# Teensy.net
KiCad netlist of a schematic drawn in Altium Designer
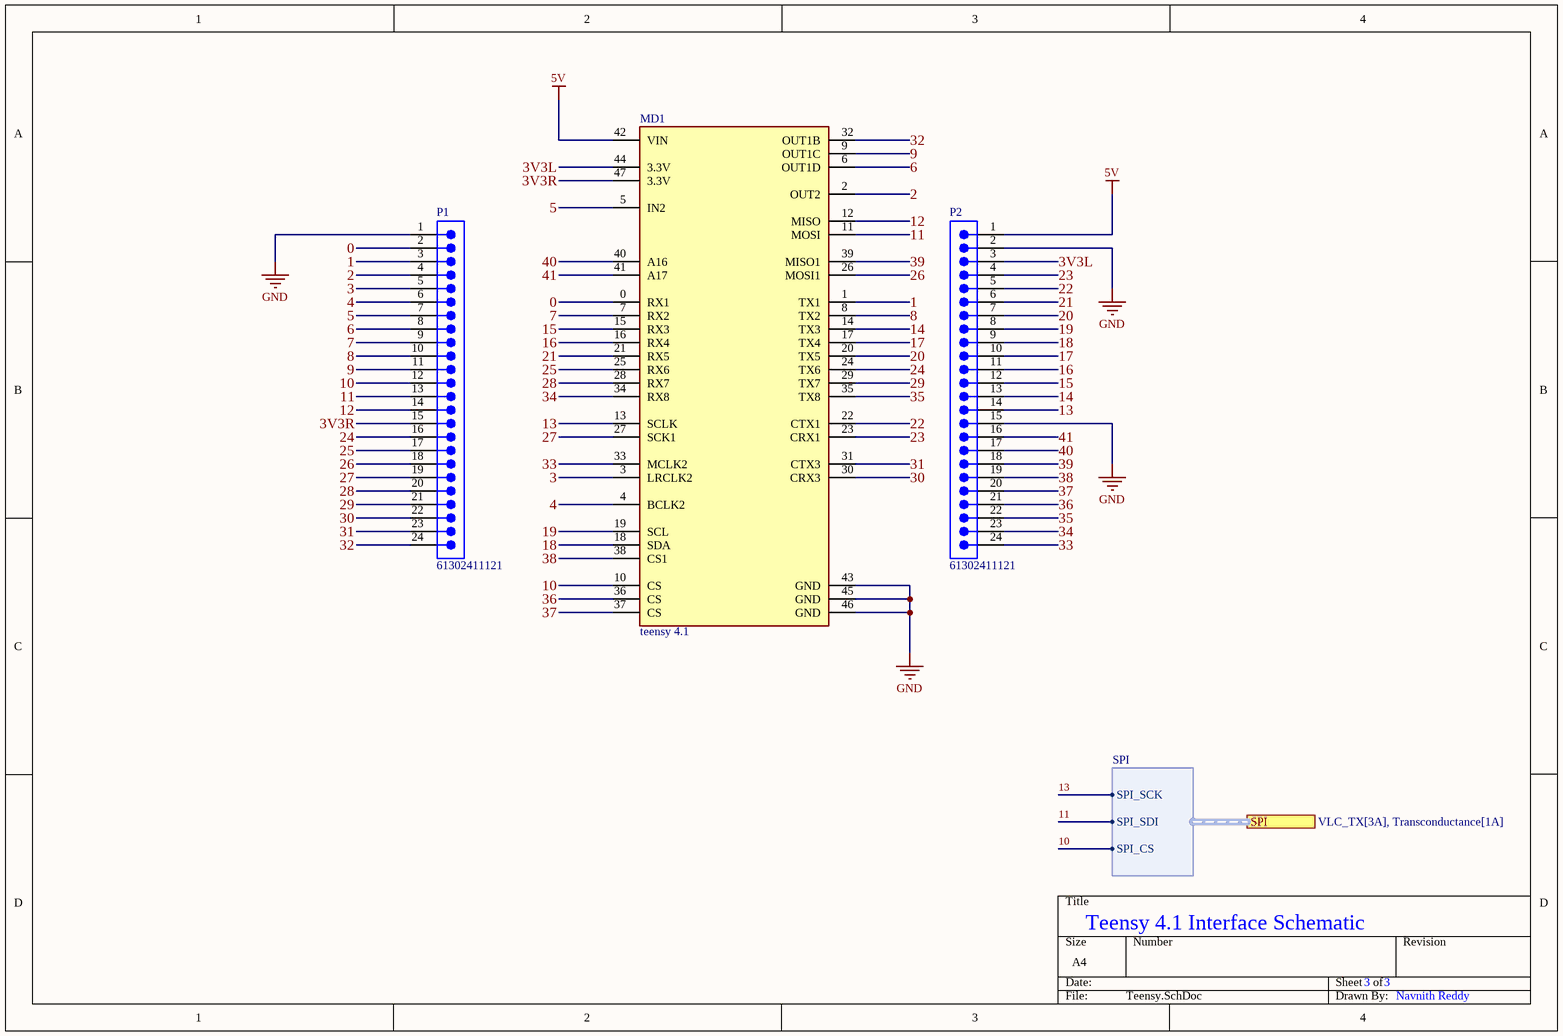
[diagram p0: Teensy.SchDoc]

(export (version "E")
  (design (tool "Eeschema 10.0.6"))
  (components
    (comp (ref "MD1")
      (value "teensy 4.1")
      (footprint "FP-DEV-16996-MFG")
      (description "TEENSY 4.1 (HEADERS)")
      (libsource (lib "Altium Content Vault") (part "080115a1ce54750370cf87ec145ee29"))
    )
    (comp (ref "P1")
      (value "61302411121")
      (footprint "61302411121")
      (libsource (lib "Altium Content Vault") (part "Header_Male_1R_24P"))
    )
    (comp (ref "P2")
      (value "61302411121")
      (footprint "61302411121")
      (libsource (lib "Altium Content Vault") (part "Header_Male_1R_24P"))
    )
  )
  (nets
    (net (code "2") (name "/0") (class "Default")
      (node (ref "MD1") (pin "0") (pinfunction "RX1_0") (pintype "passive"))
      (node (ref "P1") (pin "2") (pinfunction "2_2") (pintype "passive"))
    )
    (net (code "3") (name "/1") (class "Default")
      (node (ref "MD1") (pin "1") (pinfunction "TX1_1") (pintype "passive"))
      (node (ref "P1") (pin "3") (pinfunction "3_3") (pintype "passive"))
    )
    (net (code "4") (name "/2") (class "Default")
      (node (ref "MD1") (pin "2") (pinfunction "OUT2_2") (pintype "passive"))
      (node (ref "P1") (pin "4") (pinfunction "4_4") (pintype "passive"))
    )
    (net (code "5") (name "/3") (class "Default")
      (node (ref "MD1") (pin "3") (pinfunction "LRCLK2_3") (pintype "passive"))
      (node (ref "P1") (pin "5") (pinfunction "5_5") (pintype "passive"))
    )
    (net (code "6") (name "/3V3L") (class "Default")
      (node (ref "MD1") (pin "44") (pinfunction "3.3V_44") (pintype "passive"))
      (node (ref "P2") (pin "3") (pinfunction "3_3") (pintype "passive"))
    )
    (net (code "7") (name "/3V3R") (class "Default")
      (node (ref "MD1") (pin "47") (pinfunction "3.3V_47") (pintype "passive"))
      (node (ref "P1") (pin "15") (pinfunction "15_15") (pintype "passive"))
    )
    (net (code "8") (name "/4") (class "Default")
      (node (ref "MD1") (pin "4") (pinfunction "BCLK2_4") (pintype "passive"))
      (node (ref "P1") (pin "6") (pinfunction "6_6") (pintype "passive"))
    )
    (net (code "9") (name "/5") (class "Default")
      (node (ref "MD1") (pin "5") (pinfunction "IN2_5") (pintype "passive"))
      (node (ref "P1") (pin "7") (pinfunction "7_7") (pintype "passive"))
    )
    (net (code "10") (name "/6") (class "Default")
      (node (ref "MD1") (pin "6") (pinfunction "OUT1D_6") (pintype "passive"))
      (node (ref "P1") (pin "8") (pinfunction "8_8") (pintype "passive"))
    )
    (net (code "11") (name "/7") (class "Default")
      (node (ref "MD1") (pin "7") (pinfunction "RX2_7") (pintype "passive"))
      (node (ref "P1") (pin "9") (pinfunction "9_9") (pintype "passive"))
    )
    (net (code "12") (name "/8") (class "Default")
      (node (ref "MD1") (pin "8") (pinfunction "TX2_8") (pintype "passive"))
      (node (ref "P1") (pin "10") (pinfunction "10_10") (pintype "passive"))
    )
    (net (code "13") (name "/9") (class "Default")
      (node (ref "MD1") (pin "9") (pinfunction "OUT1C_9") (pintype "passive"))
      (node (ref "P1") (pin "11") (pinfunction "11_11") (pintype "passive"))
    )
    (net (code "14") (name "/10") (class "Default")
      (node (ref "MD1") (pin "10") (pinfunction "CS_10") (pintype "passive"))
      (node (ref "P1") (pin "12") (pinfunction "12_12") (pintype "passive"))
    )
    (net (code "15") (name "/11") (class "Default")
      (node (ref "MD1") (pin "11") (pinfunction "MOSI_11") (pintype "passive"))
      (node (ref "P1") (pin "13") (pinfunction "13_13") (pintype "passive"))
    )
    (net (code "16") (name "/12") (class "Default")
      (node (ref "MD1") (pin "12") (pinfunction "MISO_12") (pintype "passive"))
      (node (ref "P1") (pin "14") (pinfunction "14_14") (pintype "passive"))
    )
    (net (code "17") (name "/13") (class "Default")
      (node (ref "MD1") (pin "13") (pinfunction "SCLK_13") (pintype "passive"))
      (node (ref "P2") (pin "14") (pinfunction "14_14") (pintype "passive"))
    )
    (net (code "18") (name "/14") (class "Default")
      (node (ref "MD1") (pin "14") (pinfunction "TX3_14") (pintype "passive"))
      (node (ref "P2") (pin "13") (pinfunction "13_13") (pintype "passive"))
    )
    (net (code "19") (name "/15") (class "Default")
      (node (ref "MD1") (pin "15") (pinfunction "RX3_15") (pintype "passive"))
      (node (ref "P2") (pin "12") (pinfunction "12_12") (pintype "passive"))
    )
    (net (code "20") (name "/16") (class "Default")
      (node (ref "MD1") (pin "16") (pinfunction "RX4_16") (pintype "passive"))
      (node (ref "P2") (pin "11") (pinfunction "11_11") (pintype "passive"))
    )
    (net (code "21") (name "/17") (class "Default")
      (node (ref "MD1") (pin "17") (pinfunction "TX4_17") (pintype "passive"))
      (node (ref "P2") (pin "10") (pinfunction "10_10") (pintype "passive"))
    )
    (net (code "22") (name "/18") (class "Default")
      (node (ref "MD1") (pin "18") (pinfunction "SDA_18") (pintype "passive"))
      (node (ref "P2") (pin "9") (pinfunction "9_9") (pintype "passive"))
    )
    (net (code "23") (name "/19") (class "Default")
      (node (ref "MD1") (pin "19") (pinfunction "SCL_19") (pintype "passive"))
      (node (ref "P2") (pin "8") (pinfunction "8_8") (pintype "passive"))
    )
    (net (code "24") (name "/20") (class "Default")
      (node (ref "MD1") (pin "20") (pinfunction "TX5_20") (pintype "passive"))
      (node (ref "P2") (pin "7") (pinfunction "7_7") (pintype "passive"))
    )
    (net (code "25") (name "/21") (class "Default")
      (node (ref "MD1") (pin "21") (pinfunction "RX5_21") (pintype "passive"))
      (node (ref "P2") (pin "6") (pinfunction "6_6") (pintype "passive"))
    )
    (net (code "26") (name "/22") (class "Default")
      (node (ref "MD1") (pin "22") (pinfunction "CTX1_22") (pintype "passive"))
      (node (ref "P2") (pin "5") (pinfunction "5_5") (pintype "passive"))
    )
    (net (code "27") (name "/23") (class "Default")
      (node (ref "MD1") (pin "23") (pinfunction "CRX1_23") (pintype "passive"))
      (node (ref "P2") (pin "4") (pinfunction "4_4") (pintype "passive"))
    )
    (net (code "28") (name "/24") (class "Default")
      (node (ref "MD1") (pin "24") (pinfunction "TX6_24") (pintype "passive"))
      (node (ref "P1") (pin "16") (pinfunction "16_16") (pintype "passive"))
    )
    (net (code "29") (name "/25") (class "Default")
      (node (ref "MD1") (pin "25") (pinfunction "RX6_25") (pintype "passive"))
      (node (ref "P1") (pin "17") (pinfunction "17_17") (pintype "passive"))
    )
    (net (code "30") (name "/26") (class "Default")
      (node (ref "MD1") (pin "26") (pinfunction "MOSI1_26") (pintype "passive"))
      (node (ref "P1") (pin "18") (pinfunction "18_18") (pintype "passive"))
    )
    (net (code "31") (name "/27") (class "Default")
      (node (ref "MD1") (pin "27") (pinfunction "SCK1_27") (pintype "passive"))
      (node (ref "P1") (pin "19") (pinfunction "19_19") (pintype "passive"))
    )
    (net (code "32") (name "/28") (class "Default")
      (node (ref "MD1") (pin "28") (pinfunction "RX7_28") (pintype "passive"))
      (node (ref "P1") (pin "20") (pinfunction "20_20") (pintype "passive"))
    )
    (net (code "33") (name "/29") (class "Default")
      (node (ref "MD1") (pin "29") (pinfunction "TX7_29") (pintype "passive"))
      (node (ref "P1") (pin "21") (pinfunction "21_21") (pintype "passive"))
    )
    (net (code "34") (name "/30") (class "Default")
      (node (ref "MD1") (pin "30") (pinfunction "CRX3_30") (pintype "passive"))
      (node (ref "P1") (pin "22") (pinfunction "22_22") (pintype "passive"))
    )
    (net (code "35") (name "/31") (class "Default")
      (node (ref "MD1") (pin "31") (pinfunction "CTX3_31") (pintype "passive"))
      (node (ref "P1") (pin "23") (pinfunction "23_23") (pintype "passive"))
    )
    (net (code "36") (name "/32") (class "Default")
      (node (ref "MD1") (pin "32") (pinfunction "OUT1B_32") (pintype "passive"))
      (node (ref "P1") (pin "24") (pinfunction "24_24") (pintype "passive"))
    )
    (net (code "37") (name "/33") (class "Default")
      (node (ref "MD1") (pin "33") (pinfunction "MCLK2_33") (pintype "passive"))
      (node (ref "P2") (pin "24") (pinfunction "24_24") (pintype "passive"))
    )
    (net (code "38") (name "/34") (class "Default")
      (node (ref "MD1") (pin "34") (pinfunction "RX8_34") (pintype "passive"))
      (node (ref "P2") (pin "23") (pinfunction "23_23") (pintype "passive"))
    )
    (net (code "39") (name "/35") (class "Default")
      (node (ref "MD1") (pin "35") (pinfunction "TX8_35") (pintype "passive"))
      (node (ref "P2") (pin "22") (pinfunction "22_22") (pintype "passive"))
    )
    (net (code "40") (name "/36") (class "Default")
      (node (ref "MD1") (pin "36") (pinfunction "CS_36") (pintype "passive"))
      (node (ref "P2") (pin "21") (pinfunction "21_21") (pintype "passive"))
    )
    (net (code "41") (name "/37") (class "Default")
      (node (ref "MD1") (pin "37") (pinfunction "CS_37") (pintype "passive"))
      (node (ref "P2") (pin "20") (pinfunction "20_20") (pintype "passive"))
    )
    (net (code "42") (name "/38") (class "Default")
      (node (ref "MD1") (pin "38") (pinfunction "CS1_38") (pintype "passive"))
      (node (ref "P2") (pin "19") (pinfunction "19_19") (pintype "passive"))
    )
    (net (code "43") (name "/39") (class "Default")
      (node (ref "MD1") (pin "39") (pinfunction "MISO1_39") (pintype "passive"))
      (node (ref "P2") (pin "18") (pinfunction "18_18") (pintype "passive"))
    )
    (net (code "44") (name "/40") (class "Default")
      (node (ref "MD1") (pin "40") (pinfunction "A16_40") (pintype "passive"))
      (node (ref "P2") (pin "17") (pinfunction "17_17") (pintype "passive"))
    )
    (net (code "45") (name "/41") (class "Default")
      (node (ref "MD1") (pin "41") (pinfunction "A17_41") (pintype "passive"))
      (node (ref "P2") (pin "16") (pinfunction "16_16") (pintype "passive"))
    )
    (net (code "47") (name "5V") (class "Default")
      (node (ref "MD1") (pin "42") (pinfunction "VIN_42") (pintype "passive"))
      (node (ref "P2") (pin "1") (pinfunction "1_1") (pintype "passive"))
    )
    (net (code "48") (name "GND") (class "Default")
      (node (ref "MD1") (pin "43") (pinfunction "GND_43") (pintype "passive"))
      (node (ref "MD1") (pin "45") (pinfunction "GND_45") (pintype "passive"))
      (node (ref "MD1") (pin "46") (pinfunction "GND_46") (pintype "passive"))
      (node (ref "P1") (pin "1") (pinfunction "1_1") (pintype "passive"))
      (node (ref "P2") (pin "15") (pinfunction "15_15") (pintype "passive"))
      (node (ref "P2") (pin "2") (pinfunction "2_2") (pintype "passive"))
    )
  )
)
